# SEN0177.net
KiCad netlist of a schematic drawn in EAGLE
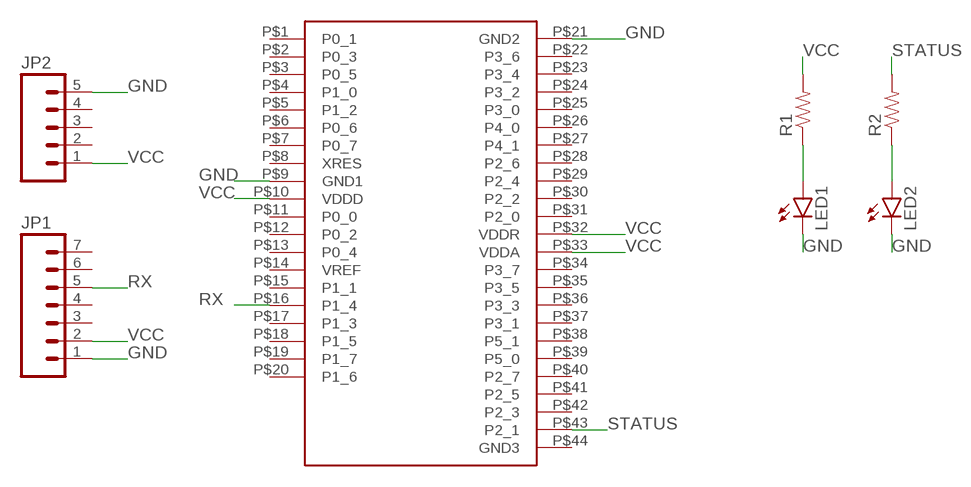
[diagram p0: schematic, sheet 1]

(export (version "E")
  (design (tool "Eeschema 10.0.6"))
  (components
    (comp (ref "JP1")
      (value "M07LONGPADS")
      (footprint "eagle-import:1X07_LONGPADS")
      (libsource (lib "eagle-import") (part "M07LONGPADS"))
    )
    (comp (ref "JP2")
      (value "M05PTH_LONGPADS")
      (footprint "eagle-import:1X05_LONGPADS")
      (libsource (lib "eagle-import") (part "M05PTH_LONGPADS"))
    )
    (comp (ref "LED1")
      (value "LED3MM")
      (footprint "eagle-import:LED3MM")
      (libsource (lib "eagle-import") (part "LED3MM"))
    )
    (comp (ref "LED2")
      (value "LED3MM")
      (footprint "eagle-import:LED3MM")
      (libsource (lib "eagle-import") (part "LED3MM"))
    )
    (comp (ref "R1")
      (value "RESISTORPTH-1/4W")
      (footprint "eagle-import:AXIAL-0.4")
      (libsource (lib "eagle-import") (part "RESISTORPTH-1/4W"))
    )
    (comp (ref "R2")
      (value "RESISTORPTH-1/4W")
      (footprint "eagle-import:AXIAL-0.4")
      (libsource (lib "eagle-import") (part "RESISTORPTH-1/4W"))
    )
    (comp (ref "U$1")
      (value "CYBLE_MODULE")
      (footprint "eagle-import:CYBLE_MODULE")
      (libsource (lib "eagle-import") (part "CYBLE_MODULE"))
    )
  )
  (nets
    (net (code "1") (name "/GND") (class "Default")
      (node (ref "JP1") (pin "1") (pinfunction "1_1") (pintype "passive"))
      (node (ref "JP2") (pin "5") (pinfunction "5_5") (pintype "passive"))
      (node (ref "LED1") (pin "K") (pinfunction "C_K") (pintype "passive"))
      (node (ref "LED2") (pin "K") (pinfunction "C_K") (pintype "passive"))
      (node (ref "U$1") (pin "P$21") (pinfunction "GND2_P$21") (pintype "bidirectional"))
      (node (ref "U$1") (pin "P$9") (pinfunction "GND1_P$9") (pintype "bidirectional"))
    )
    (net (code "2") (name "/RX") (class "Default")
      (node (ref "JP1") (pin "5") (pinfunction "5_5") (pintype "passive"))
      (node (ref "U$1") (pin "P$16") (pinfunction "P1_4_P$16") (pintype "bidirectional"))
    )
    (net (code "3") (name "/STATUS") (class "Default")
      (node (ref "R2") (pin "P$2") (pinfunction "2_P$2") (pintype "passive"))
      (node (ref "U$1") (pin "P$43") (pinfunction "P2_1_P$43") (pintype "bidirectional"))
    )
    (net (code "4") (name "/VCC") (class "Default")
      (node (ref "JP1") (pin "2") (pinfunction "2_2") (pintype "passive"))
      (node (ref "JP2") (pin "1") (pinfunction "1_1") (pintype "passive"))
      (node (ref "R1") (pin "P$2") (pinfunction "2_P$2") (pintype "passive"))
      (node (ref "U$1") (pin "P$10") (pinfunction "VDDD_P$10") (pintype "bidirectional"))
      (node (ref "U$1") (pin "P$32") (pinfunction "VDDR_P$32") (pintype "bidirectional"))
      (node (ref "U$1") (pin "P$33") (pinfunction "VDDA_P$33") (pintype "bidirectional"))
    )
    (net (code "5") (name "Net-(R1-1)") (class "Default")
      (node (ref "LED1") (pin "A") (pinfunction "A_A") (pintype "passive"))
      (node (ref "R1") (pin "P$1") (pinfunction "1_P$1") (pintype "passive"))
    )
    (net (code "6") (name "Net-(R2-1)") (class "Default")
      (node (ref "LED2") (pin "A") (pinfunction "A_A") (pintype "passive"))
      (node (ref "R2") (pin "P$1") (pinfunction "1_P$1") (pintype "passive"))
    )
    (net (code "7") (name "unconnected-(JP1-Pad3)") (class "Default")
      (node (ref "JP1") (pin "3") (pinfunction "3_3") (pintype "passive"))
    )
    (net (code "8") (name "unconnected-(JP1-Pad4)") (class "Default")
      (node (ref "JP1") (pin "4") (pinfunction "4_4") (pintype "passive"))
    )
    (net (code "9") (name "unconnected-(JP1-Pad6)") (class "Default")
      (node (ref "JP1") (pin "6") (pinfunction "6_6") (pintype "passive"))
    )
    (net (code "10") (name "unconnected-(JP1-Pad7)") (class "Default")
      (node (ref "JP1") (pin "7") (pinfunction "7_7") (pintype "passive"))
    )
    (net (code "11") (name "unconnected-(JP2-Pad2)") (class "Default")
      (node (ref "JP2") (pin "2") (pinfunction "2_2") (pintype "passive"))
    )
    (net (code "12") (name "unconnected-(JP2-Pad3)") (class "Default")
      (node (ref "JP2") (pin "3") (pinfunction "3_3") (pintype "passive"))
    )
    (net (code "13") (name "unconnected-(JP2-Pad4)") (class "Default")
      (node (ref "JP2") (pin "4") (pinfunction "4_4") (pintype "passive"))
    )
    (net (code "14") (name "unconnected-(U$1-GND3-PadP$44)") (class "Default")
      (node (ref "U$1") (pin "P$44") (pinfunction "GND3_P$44") (pintype "bidirectional"))
    )
    (net (code "15") (name "unconnected-(U$1-P0_0-PadP$11)") (class "Default")
      (node (ref "U$1") (pin "P$11") (pinfunction "P0_0_P$11") (pintype "bidirectional"))
    )
    (net (code "16") (name "unconnected-(U$1-P0_1-PadP$1)") (class "Default")
      (node (ref "U$1") (pin "P$1") (pinfunction "P0_1_P$1") (pintype "bidirectional"))
    )
    (net (code "17") (name "unconnected-(U$1-P0_2-PadP$12)") (class "Default")
      (node (ref "U$1") (pin "P$12") (pinfunction "P0_2_P$12") (pintype "bidirectional"))
    )
    (net (code "18") (name "unconnected-(U$1-P0_3-PadP$2)") (class "Default")
      (node (ref "U$1") (pin "P$2") (pinfunction "P0_3_P$2") (pintype "bidirectional"))
    )
    (net (code "19") (name "unconnected-(U$1-P0_4-PadP$13)") (class "Default")
      (node (ref "U$1") (pin "P$13") (pinfunction "P0_4_P$13") (pintype "bidirectional"))
    )
    (net (code "20") (name "unconnected-(U$1-P0_5-PadP$3)") (class "Default")
      (node (ref "U$1") (pin "P$3") (pinfunction "P0_5_P$3") (pintype "bidirectional"))
    )
    (net (code "21") (name "unconnected-(U$1-P0_6-PadP$6)") (class "Default")
      (node (ref "U$1") (pin "P$6") (pinfunction "P0_6_P$6") (pintype "bidirectional"))
    )
    (net (code "22") (name "unconnected-(U$1-P0_7-PadP$7)") (class "Default")
      (node (ref "U$1") (pin "P$7") (pinfunction "P0_7_P$7") (pintype "bidirectional"))
    )
    (net (code "23") (name "unconnected-(U$1-P1_0-PadP$4)") (class "Default")
      (node (ref "U$1") (pin "P$4") (pinfunction "P1_0_P$4") (pintype "bidirectional"))
    )
    (net (code "24") (name "unconnected-(U$1-P1_1-PadP$15)") (class "Default")
      (node (ref "U$1") (pin "P$15") (pinfunction "P1_1_P$15") (pintype "bidirectional"))
    )
    (net (code "25") (name "unconnected-(U$1-P1_2-PadP$5)") (class "Default")
      (node (ref "U$1") (pin "P$5") (pinfunction "P1_2_P$5") (pintype "bidirectional"))
    )
    (net (code "26") (name "unconnected-(U$1-P1_3-PadP$17)") (class "Default")
      (node (ref "U$1") (pin "P$17") (pinfunction "P1_3_P$17") (pintype "bidirectional"))
    )
    (net (code "27") (name "unconnected-(U$1-P1_5-PadP$18)") (class "Default")
      (node (ref "U$1") (pin "P$18") (pinfunction "P1_5_P$18") (pintype "bidirectional"))
    )
    (net (code "28") (name "unconnected-(U$1-P1_6-PadP$20)") (class "Default")
      (node (ref "U$1") (pin "P$20") (pinfunction "P1_6_P$20") (pintype "bidirectional"))
    )
    (net (code "29") (name "unconnected-(U$1-P1_7-PadP$19)") (class "Default")
      (node (ref "U$1") (pin "P$19") (pinfunction "P1_7_P$19") (pintype "bidirectional"))
    )
    (net (code "30") (name "unconnected-(U$1-P2_0-PadP$31)") (class "Default")
      (node (ref "U$1") (pin "P$31") (pinfunction "P2_0_P$31") (pintype "bidirectional"))
    )
    (net (code "31") (name "unconnected-(U$1-P2_2-PadP$30)") (class "Default")
      (node (ref "U$1") (pin "P$30") (pinfunction "P2_2_P$30") (pintype "bidirectional"))
    )
    (net (code "32") (name "unconnected-(U$1-P2_3-PadP$42)") (class "Default")
      (node (ref "U$1") (pin "P$42") (pinfunction "P2_3_P$42") (pintype "bidirectional"))
    )
    (net (code "33") (name "unconnected-(U$1-P2_4-PadP$29)") (class "Default")
      (node (ref "U$1") (pin "P$29") (pinfunction "P2_4_P$29") (pintype "bidirectional"))
    )
    (net (code "34") (name "unconnected-(U$1-P2_5-PadP$41)") (class "Default")
      (node (ref "U$1") (pin "P$41") (pinfunction "P2_5_P$41") (pintype "bidirectional"))
    )
    (net (code "35") (name "unconnected-(U$1-P2_6-PadP$28)") (class "Default")
      (node (ref "U$1") (pin "P$28") (pinfunction "P2_6_P$28") (pintype "bidirectional"))
    )
    (net (code "36") (name "unconnected-(U$1-P2_7-PadP$40)") (class "Default")
      (node (ref "U$1") (pin "P$40") (pinfunction "P2_7_P$40") (pintype "bidirectional"))
    )
    (net (code "37") (name "unconnected-(U$1-P3_0-PadP$25)") (class "Default")
      (node (ref "U$1") (pin "P$25") (pinfunction "P3_0_P$25") (pintype "bidirectional"))
    )
    (net (code "38") (name "unconnected-(U$1-P3_1-PadP$37)") (class "Default")
      (node (ref "U$1") (pin "P$37") (pinfunction "P3_1_P$37") (pintype "bidirectional"))
    )
    (net (code "39") (name "unconnected-(U$1-P3_2-PadP$24)") (class "Default")
      (node (ref "U$1") (pin "P$24") (pinfunction "P3_2_P$24") (pintype "bidirectional"))
    )
    (net (code "40") (name "unconnected-(U$1-P3_3-PadP$36)") (class "Default")
      (node (ref "U$1") (pin "P$36") (pinfunction "P3_3_P$36") (pintype "bidirectional"))
    )
    (net (code "41") (name "unconnected-(U$1-P3_4-PadP$23)") (class "Default")
      (node (ref "U$1") (pin "P$23") (pinfunction "P3_4_P$23") (pintype "bidirectional"))
    )
    (net (code "42") (name "unconnected-(U$1-P3_5-PadP$35)") (class "Default")
      (node (ref "U$1") (pin "P$35") (pinfunction "P3_5_P$35") (pintype "bidirectional"))
    )
    (net (code "43") (name "unconnected-(U$1-P3_6-PadP$22)") (class "Default")
      (node (ref "U$1") (pin "P$22") (pinfunction "P3_6_P$22") (pintype "bidirectional"))
    )
    (net (code "44") (name "unconnected-(U$1-P3_7-PadP$34)") (class "Default")
      (node (ref "U$1") (pin "P$34") (pinfunction "P3_7_P$34") (pintype "bidirectional"))
    )
    (net (code "45") (name "unconnected-(U$1-P4_0-PadP$26)") (class "Default")
      (node (ref "U$1") (pin "P$26") (pinfunction "P4_0_P$26") (pintype "bidirectional"))
    )
    (net (code "46") (name "unconnected-(U$1-P4_1-PadP$27)") (class "Default")
      (node (ref "U$1") (pin "P$27") (pinfunction "P4_1_P$27") (pintype "bidirectional"))
    )
    (net (code "47") (name "unconnected-(U$1-P5_0-PadP$39)") (class "Default")
      (node (ref "U$1") (pin "P$39") (pinfunction "P5_0_P$39") (pintype "bidirectional"))
    )
    (net (code "48") (name "unconnected-(U$1-P5_1-PadP$38)") (class "Default")
      (node (ref "U$1") (pin "P$38") (pinfunction "P5_1_P$38") (pintype "bidirectional"))
    )
    (net (code "49") (name "unconnected-(U$1-VREF-PadP$14)") (class "Default")
      (node (ref "U$1") (pin "P$14") (pinfunction "VREF_P$14") (pintype "bidirectional"))
    )
    (net (code "50") (name "unconnected-(U$1-XRES-PadP$8)") (class "Default")
      (node (ref "U$1") (pin "P$8") (pinfunction "XRES_P$8") (pintype "bidirectional"))
    )
  )
)
